# RAM1_top.net
KiCad netlist of a schematic drawn in Altium Designer
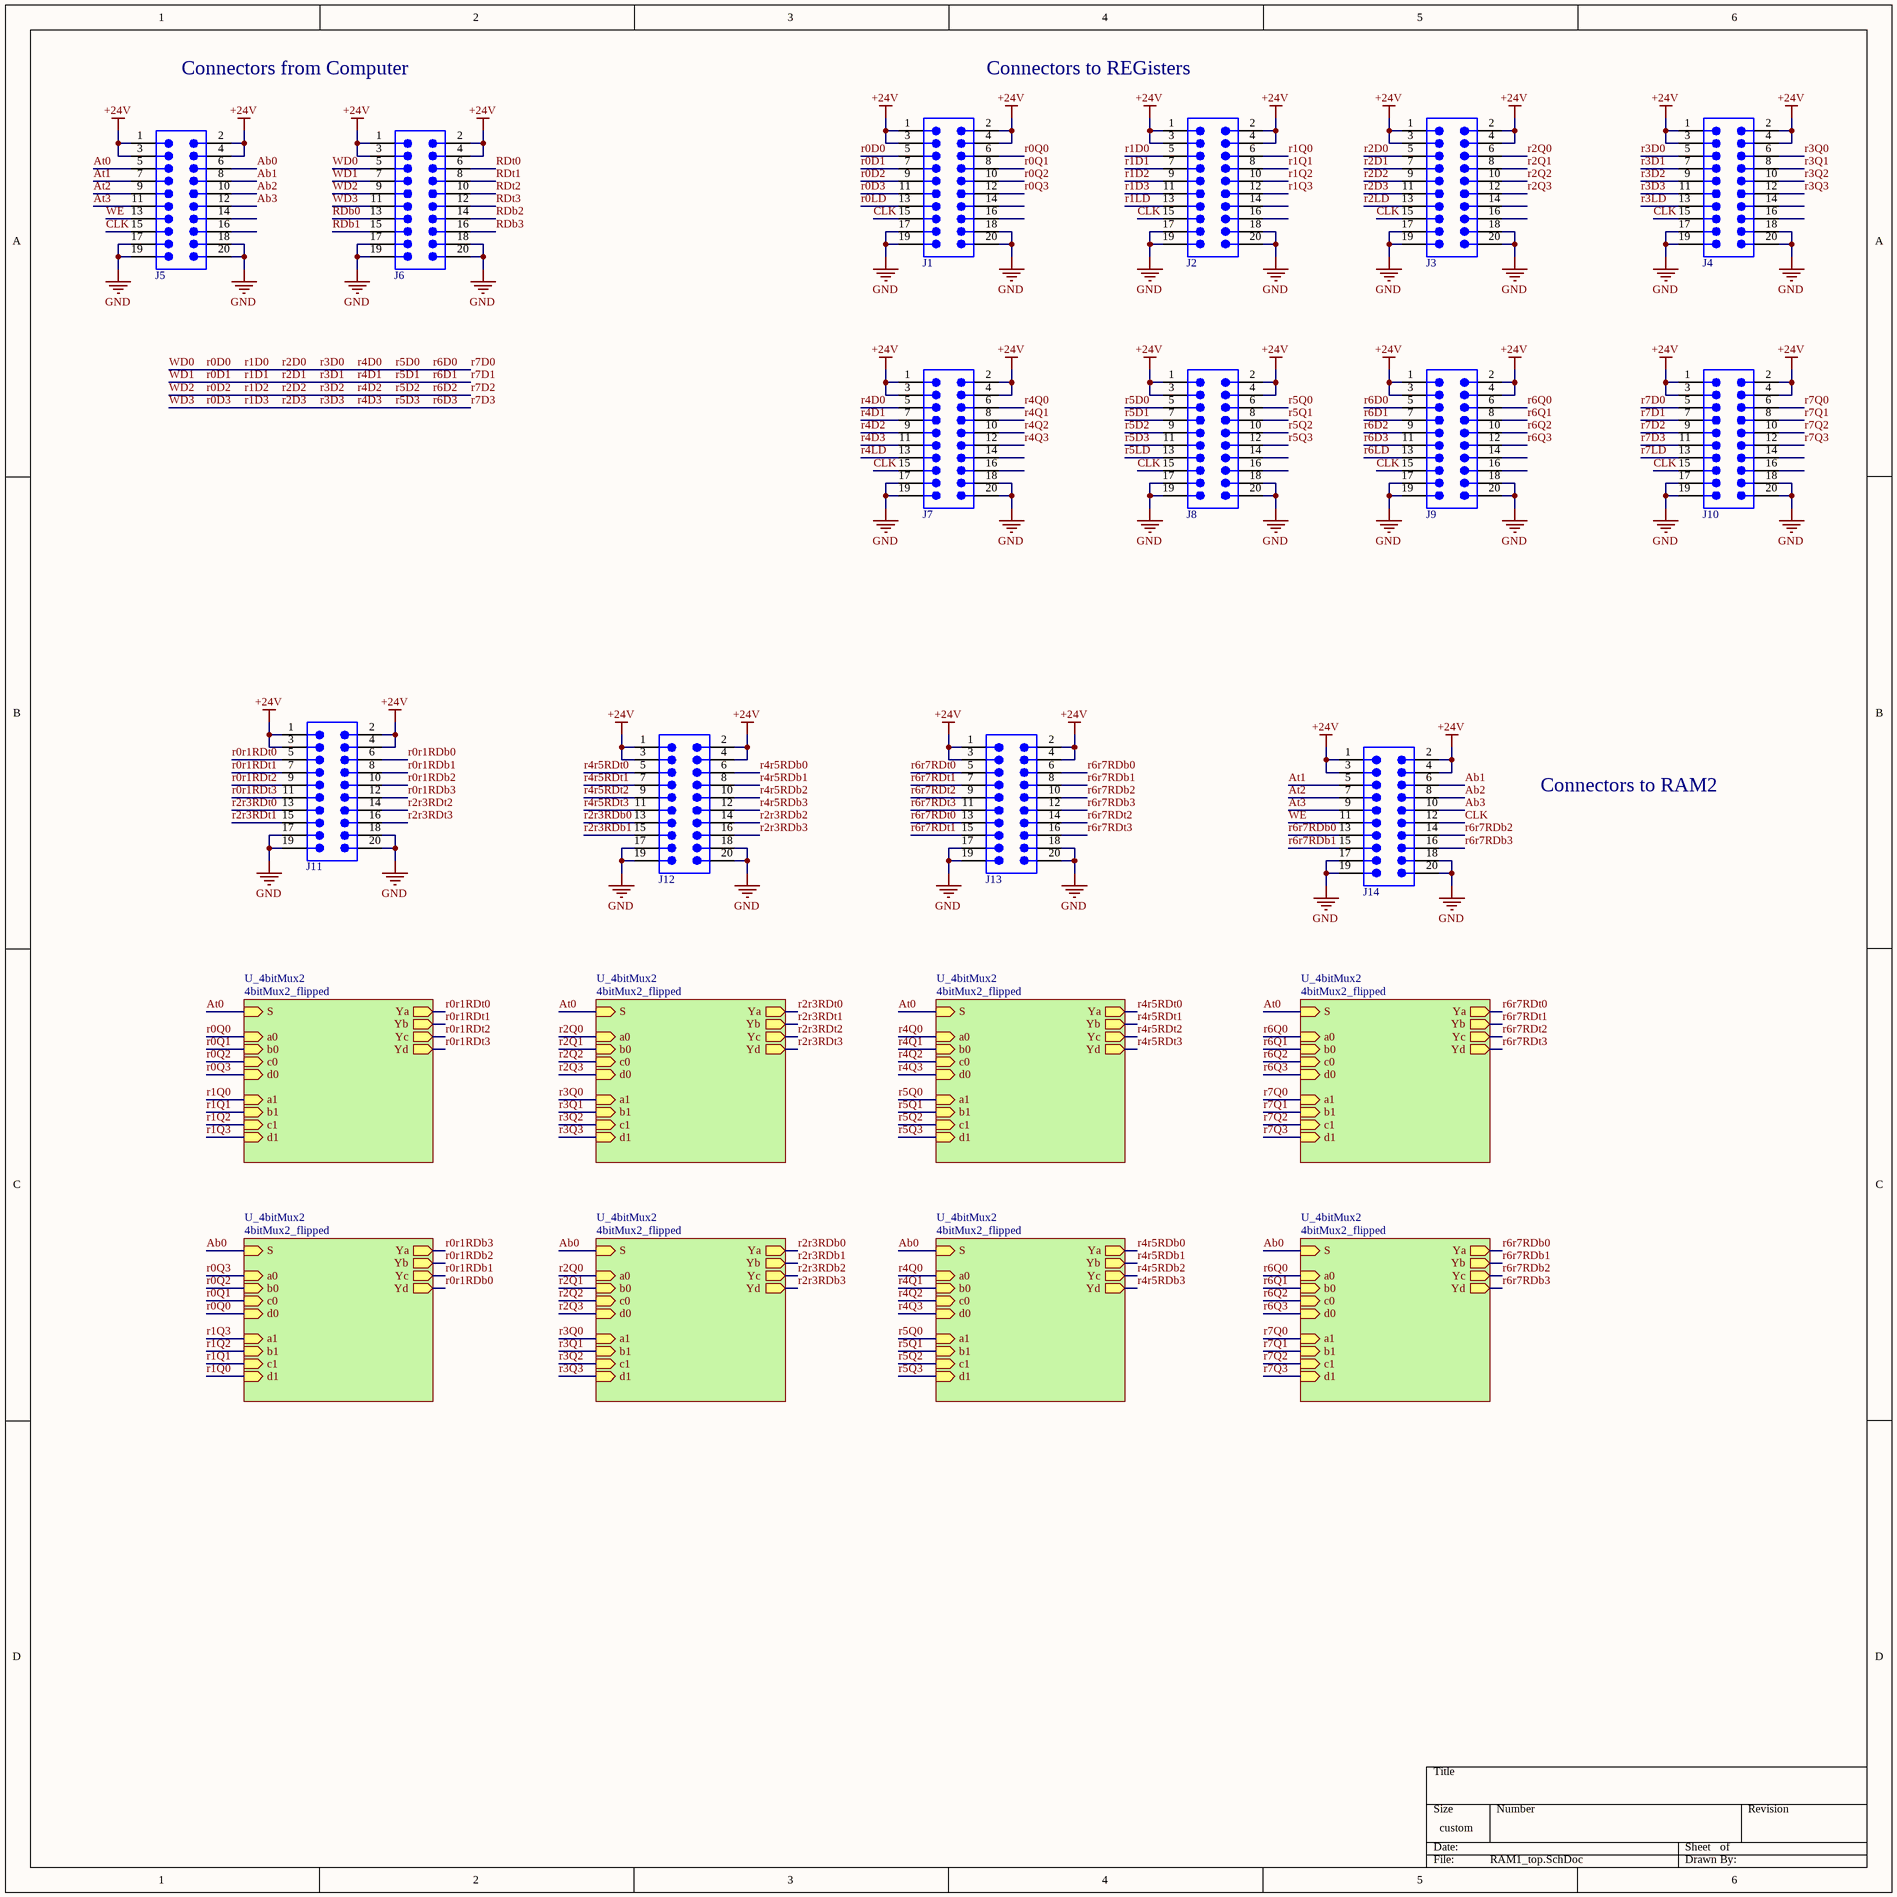
[diagram p0: RAM1_top.SchDoc]

(export (version "E")
  (design (tool "Eeschema 10.0.6"))
  (components
    (comp (ref "J1")
      (value "Con 2.54mm 10x2pos")
      (footprint "Con 2.54mm 10x2pos")
      (description "WR-BHD Straight Male, Box Header, Through Hole, 2 Rows, 20 Contacts, 2.54mm Pitch")
      (fields
        (field (name "MANUFACTURER") "Wurth Elektronik")
        (field (name "MANUFACTURER PART NUMBER") "61202021621")
      )
      (libsource (lib "RelayMachine") (part "Con 2.54mm 10x2pos"))
    )
    (comp (ref "J2")
      (value "Con 2.54mm 10x2pos")
      (footprint "Con 2.54mm 10x2pos")
      (description "WR-BHD Straight Male, Box Header, Through Hole, 2 Rows, 20 Contacts, 2.54mm Pitch")
      (fields
        (field (name "MANUFACTURER") "Wurth Elektronik")
        (field (name "MANUFACTURER PART NUMBER") "61202021621")
      )
      (libsource (lib "RelayMachine") (part "Con 2.54mm 10x2pos"))
    )
    (comp (ref "J3")
      (value "Con 2.54mm 10x2pos")
      (footprint "Con 2.54mm 10x2pos")
      (description "WR-BHD Straight Male, Box Header, Through Hole, 2 Rows, 20 Contacts, 2.54mm Pitch")
      (fields
        (field (name "MANUFACTURER") "Wurth Elektronik")
        (field (name "MANUFACTURER PART NUMBER") "61202021621")
      )
      (libsource (lib "RelayMachine") (part "Con 2.54mm 10x2pos"))
    )
    (comp (ref "J4")
      (value "Con 2.54mm 10x2pos")
      (footprint "Con 2.54mm 10x2pos")
      (description "WR-BHD Straight Male, Box Header, Through Hole, 2 Rows, 20 Contacts, 2.54mm Pitch")
      (fields
        (field (name "MANUFACTURER") "Wurth Elektronik")
        (field (name "MANUFACTURER PART NUMBER") "61202021621")
      )
      (libsource (lib "RelayMachine") (part "Con 2.54mm 10x2pos"))
    )
    (comp (ref "J5")
      (value "Con 2.54mm 10x2pos")
      (footprint "Con 2.54mm 10x2pos")
      (description "WR-BHD Straight Male, Box Header, Through Hole, 2 Rows, 20 Contacts, 2.54mm Pitch")
      (fields
        (field (name "MANUFACTURER") "Wurth Elektronik")
        (field (name "MANUFACTURER PART NUMBER") "61202021621")
      )
      (libsource (lib "RelayMachine") (part "Con 2.54mm 10x2pos"))
    )
    (comp (ref "J6")
      (value "Con 2.54mm 10x2pos")
      (footprint "Con 2.54mm 10x2pos")
      (description "WR-BHD Straight Male, Box Header, Through Hole, 2 Rows, 20 Contacts, 2.54mm Pitch")
      (fields
        (field (name "MANUFACTURER") "Wurth Elektronik")
        (field (name "MANUFACTURER PART NUMBER") "61202021621")
      )
      (libsource (lib "RelayMachine") (part "Con 2.54mm 10x2pos"))
    )
    (comp (ref "J7")
      (value "Con 2.54mm 10x2pos")
      (footprint "Con 2.54mm 10x2pos")
      (description "WR-BHD Straight Male, Box Header, Through Hole, 2 Rows, 20 Contacts, 2.54mm Pitch")
      (fields
        (field (name "MANUFACTURER") "Wurth Elektronik")
        (field (name "MANUFACTURER PART NUMBER") "61202021621")
      )
      (libsource (lib "RelayMachine") (part "Con 2.54mm 10x2pos"))
    )
    (comp (ref "J8")
      (value "Con 2.54mm 10x2pos")
      (footprint "Con 2.54mm 10x2pos")
      (description "WR-BHD Straight Male, Box Header, Through Hole, 2 Rows, 20 Contacts, 2.54mm Pitch")
      (fields
        (field (name "MANUFACTURER") "Wurth Elektronik")
        (field (name "MANUFACTURER PART NUMBER") "61202021621")
      )
      (libsource (lib "RelayMachine") (part "Con 2.54mm 10x2pos"))
    )
    (comp (ref "J9")
      (value "Con 2.54mm 10x2pos")
      (footprint "Con 2.54mm 10x2pos")
      (description "WR-BHD Straight Male, Box Header, Through Hole, 2 Rows, 20 Contacts, 2.54mm Pitch")
      (fields
        (field (name "MANUFACTURER") "Wurth Elektronik")
        (field (name "MANUFACTURER PART NUMBER") "61202021621")
      )
      (libsource (lib "RelayMachine") (part "Con 2.54mm 10x2pos"))
    )
    (comp (ref "J10")
      (value "Con 2.54mm 10x2pos")
      (footprint "Con 2.54mm 10x2pos")
      (description "WR-BHD Straight Male, Box Header, Through Hole, 2 Rows, 20 Contacts, 2.54mm Pitch")
      (fields
        (field (name "MANUFACTURER") "Wurth Elektronik")
        (field (name "MANUFACTURER PART NUMBER") "61202021621")
      )
      (libsource (lib "RelayMachine") (part "Con 2.54mm 10x2pos"))
    )
    (comp (ref "J11")
      (value "Con 2.54mm 10x2pos")
      (footprint "Con 2.54mm 10x2pos")
      (description "WR-BHD Straight Male, Box Header, Through Hole, 2 Rows, 20 Contacts, 2.54mm Pitch")
      (fields
        (field (name "MANUFACTURER") "Wurth Elektronik")
        (field (name "MANUFACTURER PART NUMBER") "61202021621")
      )
      (libsource (lib "RelayMachine") (part "Con 2.54mm 10x2pos"))
    )
    (comp (ref "J12")
      (value "Con 2.54mm 10x2pos")
      (footprint "Con 2.54mm 10x2pos")
      (description "WR-BHD Straight Male, Box Header, Through Hole, 2 Rows, 20 Contacts, 2.54mm Pitch")
      (fields
        (field (name "MANUFACTURER") "Wurth Elektronik")
        (field (name "MANUFACTURER PART NUMBER") "61202021621")
      )
      (libsource (lib "RelayMachine") (part "Con 2.54mm 10x2pos"))
    )
    (comp (ref "J13")
      (value "Con 2.54mm 10x2pos")
      (footprint "Con 2.54mm 10x2pos")
      (description "WR-BHD Straight Male, Box Header, Through Hole, 2 Rows, 20 Contacts, 2.54mm Pitch")
      (fields
        (field (name "MANUFACTURER") "Wurth Elektronik")
        (field (name "MANUFACTURER PART NUMBER") "61202021621")
      )
      (libsource (lib "RelayMachine") (part "Con 2.54mm 10x2pos"))
    )
    (comp (ref "J14")
      (value "Con 2.54mm 10x2pos")
      (footprint "Con 2.54mm 10x2pos")
      (description "WR-BHD Straight Male, Box Header, Through Hole, 2 Rows, 20 Contacts, 2.54mm Pitch")
      (fields
        (field (name "MANUFACTURER") "Wurth Elektronik")
        (field (name "MANUFACTURER PART NUMBER") "61202021621")
      )
      (libsource (lib "RelayMachine") (part "Con 2.54mm 10x2pos"))
    )
  )
  (nets
    (net (code "1") (name "+24V") (class "Default")
      (node (ref "J1") (pin "1") (pinfunction "1_1") (pintype "passive"))
      (node (ref "J1") (pin "2") (pinfunction "2_2") (pintype "passive"))
      (node (ref "J1") (pin "3") (pinfunction "3_3") (pintype "passive"))
      (node (ref "J1") (pin "4") (pinfunction "4_4") (pintype "passive"))
      (node (ref "J10") (pin "1") (pinfunction "1_1") (pintype "passive"))
      (node (ref "J10") (pin "2") (pinfunction "2_2") (pintype "passive"))
      (node (ref "J10") (pin "3") (pinfunction "3_3") (pintype "passive"))
      (node (ref "J10") (pin "4") (pinfunction "4_4") (pintype "passive"))
      (node (ref "J11") (pin "1") (pinfunction "1_1") (pintype "passive"))
      (node (ref "J11") (pin "2") (pinfunction "2_2") (pintype "passive"))
      (node (ref "J11") (pin "3") (pinfunction "3_3") (pintype "passive"))
      (node (ref "J11") (pin "4") (pinfunction "4_4") (pintype "passive"))
      (node (ref "J12") (pin "1") (pinfunction "1_1") (pintype "passive"))
      (node (ref "J12") (pin "2") (pinfunction "2_2") (pintype "passive"))
      (node (ref "J12") (pin "3") (pinfunction "3_3") (pintype "passive"))
      (node (ref "J12") (pin "4") (pinfunction "4_4") (pintype "passive"))
      (node (ref "J13") (pin "1") (pinfunction "1_1") (pintype "passive"))
      (node (ref "J13") (pin "2") (pinfunction "2_2") (pintype "passive"))
      (node (ref "J13") (pin "3") (pinfunction "3_3") (pintype "passive"))
      (node (ref "J13") (pin "4") (pinfunction "4_4") (pintype "passive"))
      (node (ref "J14") (pin "1") (pinfunction "1_1") (pintype "passive"))
      (node (ref "J14") (pin "2") (pinfunction "2_2") (pintype "passive"))
      (node (ref "J14") (pin "3") (pinfunction "3_3") (pintype "passive"))
      (node (ref "J14") (pin "4") (pinfunction "4_4") (pintype "passive"))
      (node (ref "J2") (pin "1") (pinfunction "1_1") (pintype "passive"))
      (node (ref "J2") (pin "2") (pinfunction "2_2") (pintype "passive"))
      (node (ref "J2") (pin "3") (pinfunction "3_3") (pintype "passive"))
      (node (ref "J2") (pin "4") (pinfunction "4_4") (pintype "passive"))
      (node (ref "J3") (pin "1") (pinfunction "1_1") (pintype "passive"))
      (node (ref "J3") (pin "2") (pinfunction "2_2") (pintype "passive"))
      (node (ref "J3") (pin "3") (pinfunction "3_3") (pintype "passive"))
      (node (ref "J3") (pin "4") (pinfunction "4_4") (pintype "passive"))
      (node (ref "J4") (pin "1") (pinfunction "1_1") (pintype "passive"))
      (node (ref "J4") (pin "2") (pinfunction "2_2") (pintype "passive"))
      (node (ref "J4") (pin "3") (pinfunction "3_3") (pintype "passive"))
      (node (ref "J4") (pin "4") (pinfunction "4_4") (pintype "passive"))
      (node (ref "J5") (pin "1") (pinfunction "1_1") (pintype "passive"))
      (node (ref "J5") (pin "2") (pinfunction "2_2") (pintype "passive"))
      (node (ref "J5") (pin "3") (pinfunction "3_3") (pintype "passive"))
      (node (ref "J5") (pin "4") (pinfunction "4_4") (pintype "passive"))
      (node (ref "J6") (pin "1") (pinfunction "1_1") (pintype "passive"))
      (node (ref "J6") (pin "2") (pinfunction "2_2") (pintype "passive"))
      (node (ref "J6") (pin "3") (pinfunction "3_3") (pintype "passive"))
      (node (ref "J6") (pin "4") (pinfunction "4_4") (pintype "passive"))
      (node (ref "J7") (pin "1") (pinfunction "1_1") (pintype "passive"))
      (node (ref "J7") (pin "2") (pinfunction "2_2") (pintype "passive"))
      (node (ref "J7") (pin "3") (pinfunction "3_3") (pintype "passive"))
      (node (ref "J7") (pin "4") (pinfunction "4_4") (pintype "passive"))
      (node (ref "J8") (pin "1") (pinfunction "1_1") (pintype "passive"))
      (node (ref "J8") (pin "2") (pinfunction "2_2") (pintype "passive"))
      (node (ref "J8") (pin "3") (pinfunction "3_3") (pintype "passive"))
      (node (ref "J8") (pin "4") (pinfunction "4_4") (pintype "passive"))
      (node (ref "J9") (pin "1") (pinfunction "1_1") (pintype "passive"))
      (node (ref "J9") (pin "2") (pinfunction "2_2") (pintype "passive"))
      (node (ref "J9") (pin "3") (pinfunction "3_3") (pintype "passive"))
      (node (ref "J9") (pin "4") (pinfunction "4_4") (pintype "passive"))
    )
    (net (code "2") (name "/Ab0") (class "Default")
      (node (ref "J5") (pin "6") (pinfunction "6_6") (pintype "passive"))
    )
    (net (code "3") (name "/Ab1") (class "Default")
      (node (ref "J14") (pin "6") (pinfunction "6_6") (pintype "passive"))
      (node (ref "J5") (pin "8") (pinfunction "8_8") (pintype "passive"))
    )
    (net (code "4") (name "/Ab2") (class "Default")
      (node (ref "J14") (pin "8") (pinfunction "8_8") (pintype "passive"))
      (node (ref "J5") (pin "10") (pinfunction "10_10") (pintype "passive"))
    )
    (net (code "5") (name "/Ab3") (class "Default")
      (node (ref "J14") (pin "10") (pinfunction "10_10") (pintype "passive"))
      (node (ref "J5") (pin "12") (pinfunction "12_12") (pintype "passive"))
    )
    (net (code "6") (name "/At0") (class "Default")
      (node (ref "J5") (pin "5") (pinfunction "5_5") (pintype "passive"))
    )
    (net (code "7") (name "/At1") (class "Default")
      (node (ref "J14") (pin "5") (pinfunction "5_5") (pintype "passive"))
      (node (ref "J5") (pin "7") (pinfunction "7_7") (pintype "passive"))
    )
    (net (code "8") (name "/At2") (class "Default")
      (node (ref "J14") (pin "7") (pinfunction "7_7") (pintype "passive"))
      (node (ref "J5") (pin "9") (pinfunction "9_9") (pintype "passive"))
    )
    (net (code "9") (name "/At3") (class "Default")
      (node (ref "J14") (pin "9") (pinfunction "9_9") (pintype "passive"))
      (node (ref "J5") (pin "11") (pinfunction "11_11") (pintype "passive"))
    )
    (net (code "10") (name "/CLK") (class "Default")
      (node (ref "J1") (pin "15") (pinfunction "15_15") (pintype "passive"))
      (node (ref "J10") (pin "15") (pinfunction "15_15") (pintype "passive"))
      (node (ref "J14") (pin "12") (pinfunction "12_12") (pintype "passive"))
      (node (ref "J2") (pin "15") (pinfunction "15_15") (pintype "passive"))
      (node (ref "J3") (pin "15") (pinfunction "15_15") (pintype "passive"))
      (node (ref "J4") (pin "15") (pinfunction "15_15") (pintype "passive"))
      (node (ref "J5") (pin "15") (pinfunction "15_15") (pintype "passive"))
      (node (ref "J7") (pin "15") (pinfunction "15_15") (pintype "passive"))
      (node (ref "J8") (pin "15") (pinfunction "15_15") (pintype "passive"))
      (node (ref "J9") (pin "15") (pinfunction "15_15") (pintype "passive"))
    )
    (net (code "11") (name "/RDb0") (class "Default")
      (node (ref "J6") (pin "13") (pinfunction "13_13") (pintype "passive"))
    )
    (net (code "12") (name "/RDb1") (class "Default")
      (node (ref "J6") (pin "15") (pinfunction "15_15") (pintype "passive"))
    )
    (net (code "13") (name "/RDb2") (class "Default")
      (node (ref "J6") (pin "14") (pinfunction "14_14") (pintype "passive"))
    )
    (net (code "14") (name "/RDb3") (class "Default")
      (node (ref "J6") (pin "16") (pinfunction "16_16") (pintype "passive"))
    )
    (net (code "15") (name "/RDt0") (class "Default")
      (node (ref "J6") (pin "6") (pinfunction "6_6") (pintype "passive"))
    )
    (net (code "16") (name "/RDt1") (class "Default")
      (node (ref "J6") (pin "8") (pinfunction "8_8") (pintype "passive"))
    )
    (net (code "17") (name "/RDt2") (class "Default")
      (node (ref "J6") (pin "10") (pinfunction "10_10") (pintype "passive"))
    )
    (net (code "18") (name "/RDt3") (class "Default")
      (node (ref "J6") (pin "12") (pinfunction "12_12") (pintype "passive"))
    )
    (net (code "19") (name "/WD0") (class "Default")
      (node (ref "J1") (pin "5") (pinfunction "5_5") (pintype "passive"))
      (node (ref "J10") (pin "5") (pinfunction "5_5") (pintype "passive"))
      (node (ref "J2") (pin "5") (pinfunction "5_5") (pintype "passive"))
      (node (ref "J3") (pin "5") (pinfunction "5_5") (pintype "passive"))
      (node (ref "J4") (pin "5") (pinfunction "5_5") (pintype "passive"))
      (node (ref "J6") (pin "5") (pinfunction "5_5") (pintype "passive"))
      (node (ref "J7") (pin "5") (pinfunction "5_5") (pintype "passive"))
      (node (ref "J8") (pin "5") (pinfunction "5_5") (pintype "passive"))
      (node (ref "J9") (pin "5") (pinfunction "5_5") (pintype "passive"))
    )
    (net (code "20") (name "/WD1") (class "Default")
      (node (ref "J1") (pin "7") (pinfunction "7_7") (pintype "passive"))
      (node (ref "J10") (pin "7") (pinfunction "7_7") (pintype "passive"))
      (node (ref "J2") (pin "7") (pinfunction "7_7") (pintype "passive"))
      (node (ref "J3") (pin "7") (pinfunction "7_7") (pintype "passive"))
      (node (ref "J4") (pin "7") (pinfunction "7_7") (pintype "passive"))
      (node (ref "J6") (pin "7") (pinfunction "7_7") (pintype "passive"))
      (node (ref "J7") (pin "7") (pinfunction "7_7") (pintype "passive"))
      (node (ref "J8") (pin "7") (pinfunction "7_7") (pintype "passive"))
      (node (ref "J9") (pin "7") (pinfunction "7_7") (pintype "passive"))
    )
    (net (code "21") (name "/WD2") (class "Default")
      (node (ref "J1") (pin "9") (pinfunction "9_9") (pintype "passive"))
      (node (ref "J10") (pin "9") (pinfunction "9_9") (pintype "passive"))
      (node (ref "J2") (pin "9") (pinfunction "9_9") (pintype "passive"))
      (node (ref "J3") (pin "9") (pinfunction "9_9") (pintype "passive"))
      (node (ref "J4") (pin "9") (pinfunction "9_9") (pintype "passive"))
      (node (ref "J6") (pin "9") (pinfunction "9_9") (pintype "passive"))
      (node (ref "J7") (pin "9") (pinfunction "9_9") (pintype "passive"))
      (node (ref "J8") (pin "9") (pinfunction "9_9") (pintype "passive"))
      (node (ref "J9") (pin "9") (pinfunction "9_9") (pintype "passive"))
    )
    (net (code "22") (name "/WD3") (class "Default")
      (node (ref "J1") (pin "11") (pinfunction "11_11") (pintype "passive"))
      (node (ref "J10") (pin "11") (pinfunction "11_11") (pintype "passive"))
      (node (ref "J2") (pin "11") (pinfunction "11_11") (pintype "passive"))
      (node (ref "J3") (pin "11") (pinfunction "11_11") (pintype "passive"))
      (node (ref "J4") (pin "11") (pinfunction "11_11") (pintype "passive"))
      (node (ref "J6") (pin "11") (pinfunction "11_11") (pintype "passive"))
      (node (ref "J7") (pin "11") (pinfunction "11_11") (pintype "passive"))
      (node (ref "J8") (pin "11") (pinfunction "11_11") (pintype "passive"))
      (node (ref "J9") (pin "11") (pinfunction "11_11") (pintype "passive"))
    )
    (net (code "23") (name "/WE") (class "Default")
      (node (ref "J14") (pin "11") (pinfunction "11_11") (pintype "passive"))
      (node (ref "J5") (pin "13") (pinfunction "13_13") (pintype "passive"))
    )
    (net (code "24") (name "/r0LD") (class "Default")
      (node (ref "J1") (pin "13") (pinfunction "13_13") (pintype "passive"))
    )
    (net (code "25") (name "/r0Q0") (class "Default")
      (node (ref "J1") (pin "6") (pinfunction "6_6") (pintype "passive"))
    )
    (net (code "26") (name "/r0Q1") (class "Default")
      (node (ref "J1") (pin "8") (pinfunction "8_8") (pintype "passive"))
    )
    (net (code "27") (name "/r0Q2") (class "Default")
      (node (ref "J1") (pin "10") (pinfunction "10_10") (pintype "passive"))
    )
    (net (code "28") (name "/r0Q3") (class "Default")
      (node (ref "J1") (pin "12") (pinfunction "12_12") (pintype "passive"))
    )
    (net (code "29") (name "/r0r1RDb0") (class "Default")
      (node (ref "J11") (pin "6") (pinfunction "6_6") (pintype "passive"))
    )
    (net (code "30") (name "/r0r1RDb1") (class "Default")
      (node (ref "J11") (pin "8") (pinfunction "8_8") (pintype "passive"))
    )
    (net (code "31") (name "/r0r1RDb2") (class "Default")
      (node (ref "J11") (pin "10") (pinfunction "10_10") (pintype "passive"))
    )
    (net (code "32") (name "/r0r1RDb3") (class "Default")
      (node (ref "J11") (pin "12") (pinfunction "12_12") (pintype "passive"))
    )
    (net (code "33") (name "/r0r1RDt0") (class "Default")
      (node (ref "J11") (pin "5") (pinfunction "5_5") (pintype "passive"))
    )
    (net (code "34") (name "/r0r1RDt1") (class "Default")
      (node (ref "J11") (pin "7") (pinfunction "7_7") (pintype "passive"))
    )
    (net (code "35") (name "/r0r1RDt2") (class "Default")
      (node (ref "J11") (pin "9") (pinfunction "9_9") (pintype "passive"))
    )
    (net (code "36") (name "/r0r1RDt3") (class "Default")
      (node (ref "J11") (pin "11") (pinfunction "11_11") (pintype "passive"))
    )
    (net (code "37") (name "/r1LD") (class "Default")
      (node (ref "J2") (pin "13") (pinfunction "13_13") (pintype "passive"))
    )
    (net (code "38") (name "/r1Q0") (class "Default")
      (node (ref "J2") (pin "6") (pinfunction "6_6") (pintype "passive"))
    )
    (net (code "39") (name "/r1Q1") (class "Default")
      (node (ref "J2") (pin "8") (pinfunction "8_8") (pintype "passive"))
    )
    (net (code "40") (name "/r1Q2") (class "Default")
      (node (ref "J2") (pin "10") (pinfunction "10_10") (pintype "passive"))
    )
    (net (code "41") (name "/r1Q3") (class "Default")
      (node (ref "J2") (pin "12") (pinfunction "12_12") (pintype "passive"))
    )
    (net (code "42") (name "/r2LD") (class "Default")
      (node (ref "J3") (pin "13") (pinfunction "13_13") (pintype "passive"))
    )
    (net (code "43") (name "/r2Q0") (class "Default")
      (node (ref "J3") (pin "6") (pinfunction "6_6") (pintype "passive"))
    )
    (net (code "44") (name "/r2Q1") (class "Default")
      (node (ref "J3") (pin "8") (pinfunction "8_8") (pintype "passive"))
    )
    (net (code "45") (name "/r2Q2") (class "Default")
      (node (ref "J3") (pin "10") (pinfunction "10_10") (pintype "passive"))
    )
    (net (code "46") (name "/r2Q3") (class "Default")
      (node (ref "J3") (pin "12") (pinfunction "12_12") (pintype "passive"))
    )
    (net (code "47") (name "/r2r3RDb0") (class "Default")
      (node (ref "J12") (pin "13") (pinfunction "13_13") (pintype "passive"))
    )
    (net (code "48") (name "/r2r3RDb1") (class "Default")
      (node (ref "J12") (pin "15") (pinfunction "15_15") (pintype "passive"))
    )
    (net (code "49") (name "/r2r3RDb2") (class "Default")
      (node (ref "J12") (pin "14") (pinfunction "14_14") (pintype "passive"))
    )
    (net (code "50") (name "/r2r3RDb3") (class "Default")
      (node (ref "J12") (pin "16") (pinfunction "16_16") (pintype "passive"))
    )
    (net (code "51") (name "/r2r3RDt0") (class "Default")
      (node (ref "J11") (pin "13") (pinfunction "13_13") (pintype "passive"))
    )
    (net (code "52") (name "/r2r3RDt1") (class "Default")
      (node (ref "J11") (pin "15") (pinfunction "15_15") (pintype "passive"))
    )
    (net (code "53") (name "/r2r3RDt2") (class "Default")
      (node (ref "J11") (pin "14") (pinfunction "14_14") (pintype "passive"))
    )
    (net (code "54") (name "/r2r3RDt3") (class "Default")
      (node (ref "J11") (pin "16") (pinfunction "16_16") (pintype "passive"))
    )
    (net (code "55") (name "/r3LD") (class "Default")
      (node (ref "J4") (pin "13") (pinfunction "13_13") (pintype "passive"))
    )
    (net (code "56") (name "/r3Q0") (class "Default")
      (node (ref "J4") (pin "6") (pinfunction "6_6") (pintype "passive"))
    )
    (net (code "57") (name "/r3Q1") (class "Default")
      (node (ref "J4") (pin "8") (pinfunction "8_8") (pintype "passive"))
    )
    (net (code "58") (name "/r3Q2") (class "Default")
      (node (ref "J4") (pin "10") (pinfunction "10_10") (pintype "passive"))
    )
    (net (code "59") (name "/r3Q3") (class "Default")
      (node (ref "J4") (pin "12") (pinfunction "12_12") (pintype "passive"))
    )
    (net (code "60") (name "/r4LD") (class "Default")
      (node (ref "J7") (pin "13") (pinfunction "13_13") (pintype "passive"))
    )
    (net (code "61") (name "/r4Q0") (class "Default")
      (node (ref "J7") (pin "6") (pinfunction "6_6") (pintype "passive"))
    )
    (net (code "62") (name "/r4Q1") (class "Default")
      (node (ref "J7") (pin "8") (pinfunction "8_8") (pintype "passive"))
    )
    (net (code "63") (name "/r4Q2") (class "Default")
      (node (ref "J7") (pin "10") (pinfunction "10_10") (pintype "passive"))
    )
    (net (code "64") (name "/r4Q3") (class "Default")
      (node (ref "J7") (pin "12") (pinfunction "12_12") (pintype "passive"))
    )
    (net (code "65") (name "/r4r5RDb0") (class "Default")
      (node (ref "J12") (pin "6") (pinfunction "6_6") (pintype "passive"))
    )
    (net (code "66") (name "/r4r5RDb1") (class "Default")
      (node (ref "J12") (pin "8") (pinfunction "8_8") (pintype "passive"))
    )
    (net (code "67") (name "/r4r5RDb2") (class "Default")
      (node (ref "J12") (pin "10") (pinfunction "10_10") (pintype "passive"))
    )
    (net (code "68") (name "/r4r5RDb3") (class "Default")
      (node (ref "J12") (pin "12") (pinfunction "12_12") (pintype "passive"))
    )
    (net (code "69") (name "/r4r5RDt0") (class "Default")
      (node (ref "J12") (pin "5") (pinfunction "5_5") (pintype "passive"))
    )
    (net (code "70") (name "/r4r5RDt1") (class "Default")
      (node (ref "J12") (pin "7") (pinfunction "7_7") (pintype "passive"))
    )
    (net (code "71") (name "/r4r5RDt2") (class "Default")
      (node (ref "J12") (pin "9") (pinfunction "9_9") (pintype "passive"))
    )
    (net (code "72") (name "/r4r5RDt3") (class "Default")
      (node (ref "J12") (pin "11") (pinfunction "11_11") (pintype "passive"))
    )
    (net (code "73") (name "/r5LD") (class "Default")
      (node (ref "J8") (pin "13") (pinfunction "13_13") (pintype "passive"))
    )
    (net (code "74") (name "/r5Q0") (class "Default")
      (node (ref "J8") (pin "6") (pinfunction "6_6") (pintype "passive"))
    )
    (net (code "75") (name "/r5Q1") (class "Default")
      (node (ref "J8") (pin "8") (pinfunction "8_8") (pintype "passive"))
    )
    (net (code "76") (name "/r5Q2") (class "Default")
      (node (ref "J8") (pin "10") (pinfunction "10_10") (pintype "passive"))
    )
    (net (code "77") (name "/r5Q3") (class "Default")
      (node (ref "J8") (pin "12") (pinfunction "12_12") (pintype "passive"))
    )
    (net (code "78") (name "/r6LD") (class "Default")
      (node (ref "J9") (pin "13") (pinfunction "13_13") (pintype "passive"))
    )
    (net (code "79") (name "/r6Q0") (class "Default")
      (node (ref "J9") (pin "6") (pinfunction "6_6") (pintype "passive"))
    )
    (net (code "80") (name "/r6Q1") (class "Default")
      (node (ref "J9") (pin "8") (pinfunction "8_8") (pintype "passive"))
    )
    (net (code "81") (name "/r6Q2") (class "Default")
      (node (ref "J9") (pin "10") (pinfunction "10_10") (pintype "passive"))
    )
    (net (code "82") (name "/r6Q3") (class "Default")
      (node (ref "J9") (pin "12") (pinfunction "12_12") (pintype "passive"))
    )
    (net (code "83") (name "/r6r7RDb0") (class "Default")
      (node (ref "J13") (pin "6") (pinfunction "6_6") (pintype "passive"))
      (node (ref "J14") (pin "13") (pinfunction "13_13") (pintype "passive"))
    )
    (net (code "84") (name "/r6r7RDb1") (class "Default")
      (node (ref "J13") (pin "8") (pinfunction "8_8") (pintype "passive"))
      (node (ref "J14") (pin "15") (pinfunction "15_15") (pintype "passive"))
    )
    (net (code "85") (name "/r6r7RDb2") (class "Default")
      (node (ref "J13") (pin "10") (pinfunction "10_10") (pintype "passive"))
      (node (ref "J14") (pin "14") (pinfunction "14_14") (pintype "passive"))
    )
    (net (code "86") (name "/r6r7RDb3") (class "Default")
      (node (ref "J13") (pin "12") (pinfunction "12_12") (pintype "passive"))
      (node (ref "J14") (pin "16") (pinfunction "16_16") (pintype "passive"))
    )
    (net (code "87") (name "/r6r7RDt0") (class "Default")
      (node (ref "J13") (pin "13") (pinfunction "13_13") (pintype "passive"))
      (node (ref "J13") (pin "5") (pinfunction "5_5") (pintype "passive"))
    )
    (net (code "88") (name "/r6r7RDt1") (class "Default")
      (node (ref "J13") (pin "15") (pinfunction "15_15") (pintype "passive"))
      (node (ref "J13") (pin "7") (pinfunction "7_7") (pintype "passive"))
    )
    (net (code "89") (name "/r6r7RDt2") (class "Default")
      (node (ref "J13") (pin "14") (pinfunction "14_14") (pintype "passive"))
      (node (ref "J13") (pin "9") (pinfunction "9_9") (pintype "passive"))
    )
    (net (code "90") (name "/r6r7RDt3") (class "Default")
      (node (ref "J13") (pin "11") (pinfunction "11_11") (pintype "passive"))
      (node (ref "J13") (pin "16") (pinfunction "16_16") (pintype "passive"))
    )
    (net (code "91") (name "/r7LD") (class "Default")
      (node (ref "J10") (pin "13") (pinfunction "13_13") (pintype "passive"))
    )
    (net (code "92") (name "/r7Q0") (class "Default")
      (node (ref "J10") (pin "6") (pinfunction "6_6") (pintype "passive"))
    )
    (net (code "93") (name "/r7Q1") (class "Default")
      (node (ref "J10") (pin "8") (pinfunction "8_8") (pintype "passive"))
    )
    (net (code "94") (name "/r7Q2") (class "Default")
      (node (ref "J10") (pin "10") (pinfunction "10_10") (pintype "passive"))
    )
    (net (code "95") (name "/r7Q3") (class "Default")
      (node (ref "J10") (pin "12") (pinfunction "12_12") (pintype "passive"))
    )
    (net (code "96") (name "GND") (class "Default")
      (node (ref "J1") (pin "17") (pinfunction "17_17") (pintype "passive"))
      (node (ref "J1") (pin "18") (pinfunction "18_18") (pintype "passive"))
      (node (ref "J1") (pin "19") (pinfunction "19_19") (pintype "passive"))
      (node (ref "J1") (pin "20") (pinfunction "20_20") (pintype "passive"))
      (node (ref "J10") (pin "17") (pinfunction "17_17") (pintype "passive"))
      (node (ref "J10") (pin "18") (pinfunction "18_18") (pintype "passive"))
      (node (ref "J10") (pin "19") (pinfunction "19_19") (pintype "passive"))
      (node (ref "J10") (pin "20") (pinfunction "20_20") (pintype "passive"))
      (node (ref "J11") (pin "17") (pinfunction "17_17") (pintype "passive"))
      (node (ref "J11") (pin "18") (pinfunction "18_18") (pintype "passive"))
      (node (ref "J11") (pin "19") (pinfunction "19_19") (pintype "passive"))
      (node (ref "J11") (pin "20") (pinfunction "20_20") (pintype "passive"))
      (node (ref "J12") (pin "17") (pinfunction "17_17") (pintype "passive"))
      (node (ref "J12") (pin "18") (pinfunction "18_18") (pintype "passive"))
      (node (ref "J12") (pin "19") (pinfunction "19_19") (pintype "passive"))
      (node (ref "J12") (pin "20") (pinfunction "20_20") (pintype "passive"))
      (node (ref "J13") (pin "17") (pinfunction "17_17") (pintype "passive"))
      (node (ref "J13") (pin "18") (pinfunction "18_18") (pintype "passive"))
      (node (ref "J13") (pin "19") (pinfunction "19_19") (pintype "passive"))
      (node (ref "J13") (pin "20") (pinfunction "20_20") (pintype "passive"))
      (node (ref "J14") (pin "17") (pinfunction "17_17") (pintype "passive"))
      (node (ref "J14") (pin "18") (pinfunction "18_18") (pintype "passive"))
      (node (ref "J14") (pin "19") (pinfunction "19_19") (pintype "passive"))
      (node (ref "J14") (pin "20") (pinfunction "20_20") (pintype "passive"))
      (node (ref "J2") (pin "17") (pinfunction "17_17") (pintype "passive"))
      (node (ref "J2") (pin "18") (pinfunction "18_18") (pintype "passive"))
      (node (ref "J2") (pin "19") (pinfunction "19_19") (pintype "passive"))
      (node (ref "J2") (pin "20") (pinfunction "20_20") (pintype "passive"))
      (node (ref "J3") (pin "17") (pinfunction "17_17") (pintype "passive"))
      (node (ref "J3") (pin "18") (pinfunction "18_18") (pintype "passive"))
      (node (ref "J3") (pin "19") (pinfunction "19_19") (pintype "passive"))
      (node (ref "J3") (pin "20") (pinfunction "20_20") (pintype "passive"))
      (node (ref "J4") (pin "17") (pinfunction "17_17") (pintype "passive"))
      (node (ref "J4") (pin "18") (pinfunction "18_18") (pintype "passive"))
      (node (ref "J4") (pin "19") (pinfunction "19_19") (pintype "passive"))
      (node (ref "J4") (pin "20") (pinfunction "20_20") (pintype "passive"))
      (node (ref "J5") (pin "17") (pinfunction "17_17") (pintype "passive"))
      (node (ref "J5") (pin "18") (pinfunction "18_18") (pintype "passive"))
      (node (ref "J5") (pin "19") (pinfunction "19_19") (pintype "passive"))
      (node (ref "J5") (pin "20") (pinfunction "20_20") (pintype "passive"))
      (node (ref "J6") (pin "17") (pinfunction "17_17") (pintype "passive"))
      (node (ref "J6") (pin "18") (pinfunction "18_18") (pintype "passive"))
      (node (ref "J6") (pin "19") (pinfunction "19_19") (pintype "passive"))
      (node (ref "J6") (pin "20") (pinfunction "20_20") (pintype "passive"))
      (node (ref "J7") (pin "17") (pinfunction "17_17") (pintype "passive"))
      (node (ref "J7") (pin "18") (pinfunction "18_18") (pintype "passive"))
      (node (ref "J7") (pin "19") (pinfunction "19_19") (pintype "passive"))
      (node (ref "J7") (pin "20") (pinfunction "20_20") (pintype "passive"))
      (node (ref "J8") (pin "17") (pinfunction "17_17") (pintype "passive"))
      (node (ref "J8") (pin "18") (pinfunction "18_18") (pintype "passive"))
      (node (ref "J8") (pin "19") (pinfunction "19_19") (pintype "passive"))
      (node (ref "J8") (pin "20") (pinfunction "20_20") (pintype "passive"))
      (node (ref "J9") (pin "17") (pinfunction "17_17") (pintype "passive"))
      (node (ref "J9") (pin "18") (pinfunction "18_18") (pintype "passive"))
      (node (ref "J9") (pin "19") (pinfunction "19_19") (pintype "passive"))
      (node (ref "J9") (pin "20") (pinfunction "20_20") (pintype "passive"))
    )
    (net (code "97") (name "unconnected-(J1-Pad14)") (class "Default")
      (node (ref "J1") (pin "14") (pinfunction "14_14") (pintype "passive"))
    )
    (net (code "98") (name "unconnected-(J1-Pad16)") (class "Default")
      (node (ref "J1") (pin "16") (pinfunction "16_16") (pintype "passive"))
    )
    (net (code "99") (name "unconnected-(J2-Pad14)") (class "Default")
      (node (ref "J2") (pin "14") (pinfunction "14_14") (pintype "passive"))
    )
    (net (code "100") (name "unconnected-(J2-Pad16)") (class "Default")
      (node (ref "J2") (pin "16") (pinfunction "16_16") (pintype "passive"))
    )
    (net (code "101") (name "unconnected-(J3-Pad14)") (class "Default")
      (node (ref "J3") (pin "14") (pinfunction "14_14") (pintype "passive"))
    )
    (net (code "102") (name "unconnected-(J3-Pad16)") (class "Default")
      (node (ref "J3") (pin "16") (pinfunction "16_16") (pintype "passive"))
    )
    (net (code "103") (name "unconnected-(J4-Pad14)") (class "Default")
      (node (ref "J4") (pin "14") (pinfunction "14_14") (pintype "passive"))
    )
    (net (code "104") (name "unconnected-(J4-Pad16)") (class "Default")
      (node (ref "J4") (pin "16") (pinfunction "16_16") (pintype "passive"))
    )
    (net (code "105") (name "unconnected-(J5-Pad14)") (class "Default")
      (node (ref "J5") (pin "14") (pinfunction "14_14") (pintype "passive"))
    )
    (net (code "106") (name "unconnected-(J5-Pad16)") (class "Default")
      (node (ref "J5") (pin "16") (pinfunction "16_16") (pintype "passive"))
    )
    (net (code "107") (name "unconnected-(J7-Pad14)") (class "Default")
      (node (ref "J7") (pin "14") (pinfunction "14_14") (pintype "passive"))
    )
    (net (code "108") (name "unconnected-(J7-Pad16)") (class "Default")
      (node (ref "J7") (pin "16") (pinfunction "16_16") (pintype "passive"))
    )
    (net (code "109") (name "unconnected-(J8-Pad14)") (class "Default")
      (node (ref "J8") (pin "14") (pinfunction "14_14") (pintype "passive"))
    )
    (net (code "110") (name "unconnected-(J8-Pad16)") (class "Default")
      (node (ref "J8") (pin "16") (pinfunction "16_16") (pintype "passive"))
    )
    (net (code "111") (name "unconnected-(J9-Pad14)") (class "Default")
      (node (ref "J9") (pin "14") (pinfunction "14_14") (pintype "passive"))
    )
    (net (code "112") (name "unconnected-(J9-Pad16)") (class "Default")
      (node (ref "J9") (pin "16") (pinfunction "16_16") (pintype "passive"))
    )
    (net (code "113") (name "unconnected-(J10-Pad14)") (class "Default")
      (node (ref "J10") (pin "14") (pinfunction "14_14") (pintype "passive"))
    )
    (net (code "114") (name "unconnected-(J10-Pad16)") (class "Default")
      (node (ref "J10") (pin "16") (pinfunction "16_16") (pintype "passive"))
    )
  )
)
